# rev_a.net
KiCad netlist of a schematic drawn in EAGLE
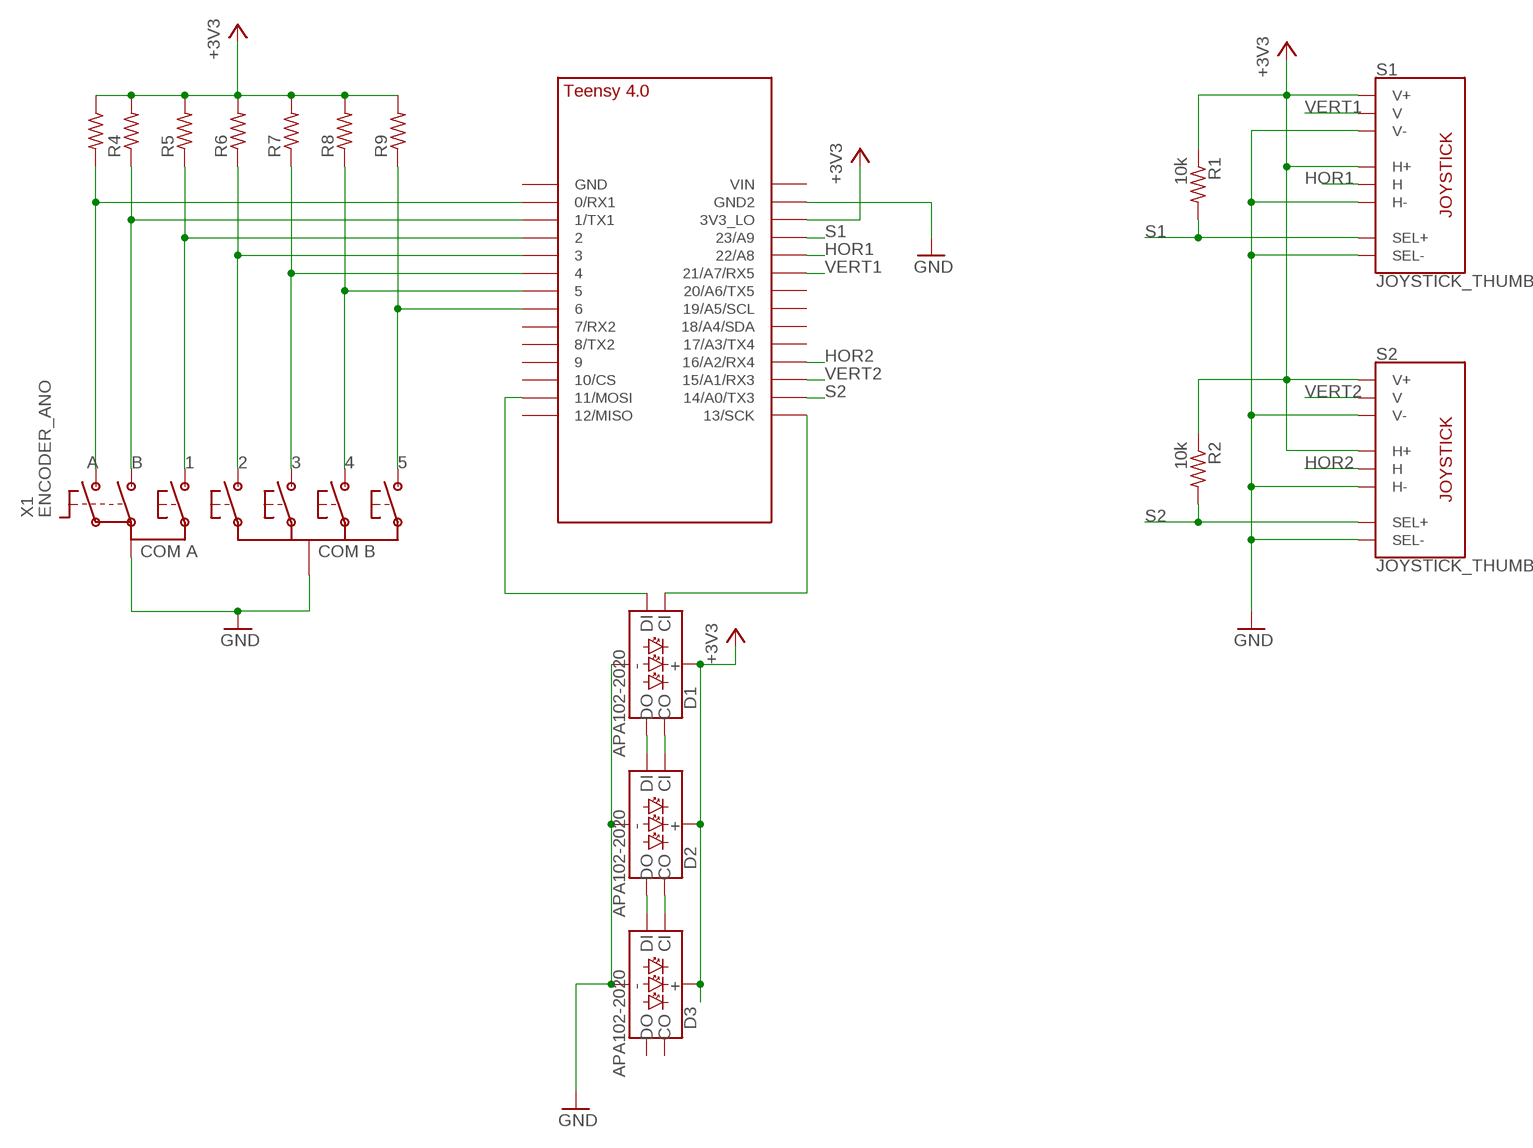
[diagram p0: schematic, sheet 1]

(export (version "E")
  (design (tool "Eeschema 10.0.6"))
  (components
    (comp (ref "D1")
      (value "APA102-2020")
      (footprint "eagle-import:APA102-2020")
      (libsource (lib "eagle-import") (part "APA102-2020"))
    )
    (comp (ref "D2")
      (value "APA102-2020")
      (footprint "eagle-import:APA102-2020")
      (libsource (lib "eagle-import") (part "APA102-2020"))
    )
    (comp (ref "D3")
      (value "APA102-2020")
      (footprint "eagle-import:APA102-2020")
      (libsource (lib "eagle-import") (part "APA102-2020"))
    )
    (comp (ref "MCU")
      (value "TEENSY_4.0-NOBOTTOM")
      (footprint "eagle-import:TEENSY_4.0-NOBOTTOM")
      (libsource (lib "eagle-import") (part "TEENSY_4.0-NOBOTTOM"))
    )
    (comp (ref "R1")
      (value "10k")
      (footprint "eagle-import:R0603")
      (libsource (lib "eagle-import") (part "R-US_R0603"))
    )
    (comp (ref "R2")
      (value "10k")
      (footprint "eagle-import:R0603")
      (libsource (lib "eagle-import") (part "R-US_R0603"))
    )
    (comp (ref "R3")
      (value "10k")
      (footprint "eagle-import:R0603")
      (libsource (lib "eagle-import") (part "R-US_R0603"))
    )
    (comp (ref "R4")
      (value "R-US_R0603")
      (footprint "eagle-import:R0603")
      (libsource (lib "eagle-import") (part "R-US_R0603"))
    )
    (comp (ref "R5")
      (value "R-US_R0603")
      (footprint "eagle-import:R0603")
      (libsource (lib "eagle-import") (part "R-US_R0603"))
    )
    (comp (ref "R6")
      (value "R-US_R0603")
      (footprint "eagle-import:R0603")
      (libsource (lib "eagle-import") (part "R-US_R0603"))
    )
    (comp (ref "R7")
      (value "R-US_R0603")
      (footprint "eagle-import:R0603")
      (libsource (lib "eagle-import") (part "R-US_R0603"))
    )
    (comp (ref "R8")
      (value "R-US_R0603")
      (footprint "eagle-import:R0603")
      (libsource (lib "eagle-import") (part "R-US_R0603"))
    )
    (comp (ref "R9")
      (value "R-US_R0603")
      (footprint "eagle-import:R0603")
      (libsource (lib "eagle-import") (part "R-US_R0603"))
    )
    (comp (ref "S1")
      (value "JOYSTICK_THUMB")
      (footprint "eagle-import:JOYSTICK")
      (libsource (lib "eagle-import") (part "JOYSTICK_THUMB"))
    )
    (comp (ref "S2")
      (value "JOYSTICK_THUMB")
      (footprint "eagle-import:JOYSTICK")
      (libsource (lib "eagle-import") (part "JOYSTICK_THUMB"))
    )
    (comp (ref "X1")
      (value "ENCODER_ANO")
      (footprint "eagle-import:ENCODER_ANO")
      (libsource (lib "eagle-import") (part "ENCODER_ANO"))
    )
  )
  (nets
    (net (code "1") (name "+3V3") (class "Default")
      (node (ref "D1") (pin "VDD") (pinfunction "VCC_VDD") (pintype "bidirectional"))
      (node (ref "D2") (pin "VDD") (pinfunction "VCC_VDD") (pintype "bidirectional"))
      (node (ref "D3") (pin "VDD") (pinfunction "VCC_VDD") (pintype "bidirectional"))
      (node (ref "MCU") (pin "3V3_LO") (pinfunction "3V3_LO_3V3_LO") (pintype "bidirectional"))
      (node (ref "R1") (pin "1") (pinfunction "1_1") (pintype "passive"))
      (node (ref "R2") (pin "1") (pinfunction "1_1") (pintype "passive"))
      (node (ref "R3") (pin "1") (pinfunction "1_1") (pintype "passive"))
      (node (ref "R4") (pin "2") (pinfunction "2_2") (pintype "passive"))
      (node (ref "R5") (pin "2") (pinfunction "2_2") (pintype "passive"))
      (node (ref "R6") (pin "2") (pinfunction "2_2") (pintype "passive"))
      (node (ref "R7") (pin "2") (pinfunction "2_2") (pintype "passive"))
      (node (ref "R8") (pin "2") (pinfunction "2_2") (pintype "passive"))
      (node (ref "R9") (pin "2") (pinfunction "2_2") (pintype "passive"))
      (node (ref "S1") (pin "H1") (pinfunction "H+_H1") (pintype "bidirectional"))
      (node (ref "S1") (pin "V1") (pinfunction "V+_V1") (pintype "bidirectional"))
      (node (ref "S2") (pin "H1") (pinfunction "H+_H1") (pintype "bidirectional"))
      (node (ref "S2") (pin "V1") (pinfunction "V+_V1") (pintype "bidirectional"))
    )
    (net (code "2") (name "/HOR1") (class "Default")
      (node (ref "MCU") (pin "22/A8") (pinfunction "22/A8_22/A8") (pintype "bidirectional"))
      (node (ref "S1") (pin "H2") (pinfunction "H_H2") (pintype "bidirectional"))
    )
    (net (code "3") (name "/HOR2") (class "Default")
      (node (ref "MCU") (pin "16/A2") (pinfunction "16/A2/RX4_16/A2") (pintype "bidirectional"))
      (node (ref "S2") (pin "H2") (pinfunction "H_H2") (pintype "bidirectional"))
    )
    (net (code "4") (name "/S1") (class "Default")
      (node (ref "MCU") (pin "23/A9") (pinfunction "23/A9_23/A9") (pintype "bidirectional"))
      (node (ref "R1") (pin "2") (pinfunction "2_2") (pintype "passive"))
      (node (ref "S1") (pin "B1A") (pinfunction "SEL+_B1A") (pintype "bidirectional"))
    )
    (net (code "5") (name "/S2") (class "Default")
      (node (ref "MCU") (pin "14/A0") (pinfunction "14/A0/TX3_14/A0") (pintype "bidirectional"))
      (node (ref "R2") (pin "2") (pinfunction "2_2") (pintype "passive"))
      (node (ref "S2") (pin "B1A") (pinfunction "SEL+_B1A") (pintype "bidirectional"))
    )
    (net (code "6") (name "/VERT1") (class "Default")
      (node (ref "MCU") (pin "21/A7") (pinfunction "21/A7/RX5_21/A7") (pintype "bidirectional"))
      (node (ref "S1") (pin "V2") (pinfunction "V_V2") (pintype "bidirectional"))
    )
    (net (code "7") (name "/VERT2") (class "Default")
      (node (ref "MCU") (pin "15/A1") (pinfunction "15/A1/RX3_15/A1") (pintype "bidirectional"))
      (node (ref "S2") (pin "V2") (pinfunction "V_V2") (pintype "bidirectional"))
    )
    (net (code "8") (name "GND") (class "Default")
      (node (ref "D1") (pin "GND") (pinfunction "GND_GND") (pintype "bidirectional"))
      (node (ref "D2") (pin "GND") (pinfunction "GND_GND") (pintype "bidirectional"))
      (node (ref "D3") (pin "GND") (pinfunction "GND_GND") (pintype "bidirectional"))
      (node (ref "MCU") (pin "GND2") (pinfunction "GND2_GND2") (pintype "bidirectional"))
      (node (ref "S1") (pin "B2A") (pinfunction "SEL-_B2A") (pintype "bidirectional"))
      (node (ref "S1") (pin "H3") (pinfunction "H-_H3") (pintype "bidirectional"))
      (node (ref "S1") (pin "V3") (pinfunction "V-_V3") (pintype "bidirectional"))
      (node (ref "S2") (pin "B2A") (pinfunction "SEL-_B2A") (pintype "bidirectional"))
      (node (ref "S2") (pin "H3") (pinfunction "H-_H3") (pintype "bidirectional"))
      (node (ref "S2") (pin "V3") (pinfunction "V-_V3") (pintype "bidirectional"))
      (node (ref "X1") (pin "COM_A") (pinfunction "COMA_COM_A") (pintype "passive"))
      (node (ref "X1") (pin "COM_B") (pinfunction "COM_B_COM_B") (pintype "passive"))
    )
    (net (code "9") (name "Net-(D1-CI)") (class "Default")
      (node (ref "D1") (pin "CKI") (pinfunction "CI_CKI") (pintype "bidirectional"))
      (node (ref "MCU") (pin "13/SCK") (pinfunction "13/SCK_13/SCK") (pintype "bidirectional"))
    )
    (net (code "10") (name "Net-(D1-CO)") (class "Default")
      (node (ref "D1") (pin "CKO") (pinfunction "CO_CKO") (pintype "bidirectional"))
      (node (ref "D2") (pin "CKI") (pinfunction "CI_CKI") (pintype "bidirectional"))
    )
    (net (code "11") (name "Net-(D1-DI)") (class "Default")
      (node (ref "D1") (pin "SDI") (pinfunction "DI_SDI") (pintype "bidirectional"))
      (node (ref "MCU") (pin "11/MOSI") (pinfunction "11/MOSI_11/MOSI") (pintype "bidirectional"))
    )
    (net (code "12") (name "Net-(D1-DO)") (class "Default")
      (node (ref "D1") (pin "SDO") (pinfunction "DO_SDO") (pintype "bidirectional"))
      (node (ref "D2") (pin "SDI") (pinfunction "DI_SDI") (pintype "bidirectional"))
    )
    (net (code "13") (name "Net-(D2-CO)") (class "Default")
      (node (ref "D2") (pin "CKO") (pinfunction "CO_CKO") (pintype "bidirectional"))
      (node (ref "D3") (pin "CKI") (pinfunction "CI_CKI") (pintype "bidirectional"))
    )
    (net (code "14") (name "Net-(D2-DO)") (class "Default")
      (node (ref "D2") (pin "SDO") (pinfunction "DO_SDO") (pintype "bidirectional"))
      (node (ref "D3") (pin "SDI") (pinfunction "DI_SDI") (pintype "bidirectional"))
    )
    (net (code "15") (name "Net-(MCU-0{slash}RX1)") (class "Default")
      (node (ref "MCU") (pin "0/RX") (pinfunction "0/RX1_0/RX") (pintype "bidirectional"))
      (node (ref "R3") (pin "2") (pinfunction "2_2") (pintype "passive"))
      (node (ref "X1") (pin "A") (pinfunction "A_A") (pintype "passive"))
    )
    (net (code "16") (name "Net-(MCU-1{slash}TX1)") (class "Default")
      (node (ref "MCU") (pin "1/TX") (pinfunction "1/TX1_1/TX") (pintype "bidirectional"))
      (node (ref "R4") (pin "1") (pinfunction "1_1") (pintype "passive"))
      (node (ref "X1") (pin "B") (pinfunction "B_B") (pintype "passive"))
    )
    (net (code "17") (name "Net-(MCU-3)") (class "Default")
      (node (ref "MCU") (pin "3/CANTX") (pinfunction "3_3/CANTX") (pintype "bidirectional"))
      (node (ref "R6") (pin "1") (pinfunction "1_1") (pintype "passive"))
      (node (ref "X1") (pin "S2") (pinfunction "S2_S2") (pintype "passive"))
    )
    (net (code "18") (name "Net-(MCU-4)") (class "Default")
      (node (ref "MCU") (pin "4/CANRX") (pinfunction "4_4/CANRX") (pintype "bidirectional"))
      (node (ref "R7") (pin "1") (pinfunction "1_1") (pintype "passive"))
      (node (ref "X1") (pin "S3") (pinfunction "S3_S3") (pintype "passive"))
    )
    (net (code "19") (name "Net-(MCU-Pad5)") (class "Default")
      (node (ref "MCU") (pin "5") (pinfunction "5_5") (pintype "bidirectional"))
      (node (ref "R8") (pin "1") (pinfunction "1_1") (pintype "passive"))
      (node (ref "X1") (pin "S4") (pinfunction "S4_S4") (pintype "passive"))
    )
    (net (code "20") (name "Net-(MCU-Pad6)") (class "Default")
      (node (ref "MCU") (pin "6") (pinfunction "6_6") (pintype "bidirectional"))
      (node (ref "R9") (pin "1") (pinfunction "1_1") (pintype "passive"))
      (node (ref "X1") (pin "S5") (pinfunction "S5_S5") (pintype "passive"))
    )
    (net (code "21") (name "Net-(X1-1)") (class "Default")
      (node (ref "MCU") (pin "2") (pinfunction "2_2") (pintype "bidirectional"))
      (node (ref "R5") (pin "1") (pinfunction "1_1") (pintype "passive"))
      (node (ref "X1") (pin "S1") (pinfunction "1_S1") (pintype "passive"))
    )
    (net (code "22") (name "unconnected-(D3-CO-PadCKO)") (class "Default")
      (node (ref "D3") (pin "CKO") (pinfunction "CO_CKO") (pintype "bidirectional"))
    )
    (net (code "23") (name "unconnected-(D3-DO-PadSDO)") (class "Default")
      (node (ref "D3") (pin "SDO") (pinfunction "DO_SDO") (pintype "bidirectional"))
    )
    (net (code "24") (name "unconnected-(MCU-7{slash}RX2-Pad7)") (class "Default")
      (node (ref "MCU") (pin "7") (pinfunction "7/RX2_7") (pintype "bidirectional"))
    )
    (net (code "25") (name "unconnected-(MCU-8{slash}TX2-Pad8)") (class "Default")
      (node (ref "MCU") (pin "8") (pinfunction "8/TX2_8") (pintype "bidirectional"))
    )
    (net (code "26") (name "unconnected-(MCU-9-Pad9{slash}CS)") (class "Default")
      (node (ref "MCU") (pin "9/CS") (pinfunction "9_9/CS") (pintype "bidirectional"))
    )
    (net (code "27") (name "unconnected-(MCU-17{slash}A3{slash}TX4-Pad17{slash}A3)") (class "Default")
      (node (ref "MCU") (pin "17/A3") (pinfunction "17/A3/TX4_17/A3") (pintype "bidirectional"))
    )
    (net (code "28") (name "unconnected-(MCU-20{slash}A6{slash}TX5-Pad20{slash}A6)") (class "Default")
      (node (ref "MCU") (pin "20/A6") (pinfunction "20/A6/TX5_20/A6") (pintype "bidirectional"))
    )
    (net (code "29") (name "unconnected-(MCU-Pad10{slash}CS)") (class "Default")
      (node (ref "MCU") (pin "10/CS") (pinfunction "10/CS_10/CS") (pintype "bidirectional"))
    )
    (net (code "30") (name "unconnected-(MCU-Pad12{slash}MISO)") (class "Default")
      (node (ref "MCU") (pin "12/MISO") (pinfunction "12/MISO_12/MISO") (pintype "bidirectional"))
    )
    (net (code "31") (name "unconnected-(MCU-Pad18{slash}A4{slash}SDA)") (class "Default")
      (node (ref "MCU") (pin "18/A4/SDA") (pinfunction "18/A4/SDA_18/A4/SDA") (pintype "bidirectional"))
    )
    (net (code "32") (name "unconnected-(MCU-Pad19{slash}A5{slash}SCL)") (class "Default")
      (node (ref "MCU") (pin "19/A5/SCL") (pinfunction "19/A5/SCL_19/A5/SCL") (pintype "bidirectional"))
    )
    (net (code "33") (name "unconnected-(MCU-PadGND)") (class "Default")
      (node (ref "MCU") (pin "GND") (pinfunction "GND_GND") (pintype "bidirectional"))
    )
    (net (code "34") (name "unconnected-(MCU-PadVIN)") (class "Default")
      (node (ref "MCU") (pin "VIN") (pinfunction "VIN_VIN") (pintype "bidirectional"))
    )
  )
)
